# CircuitBoard.net
KiCad netlist of a schematic drawn in EAGLE
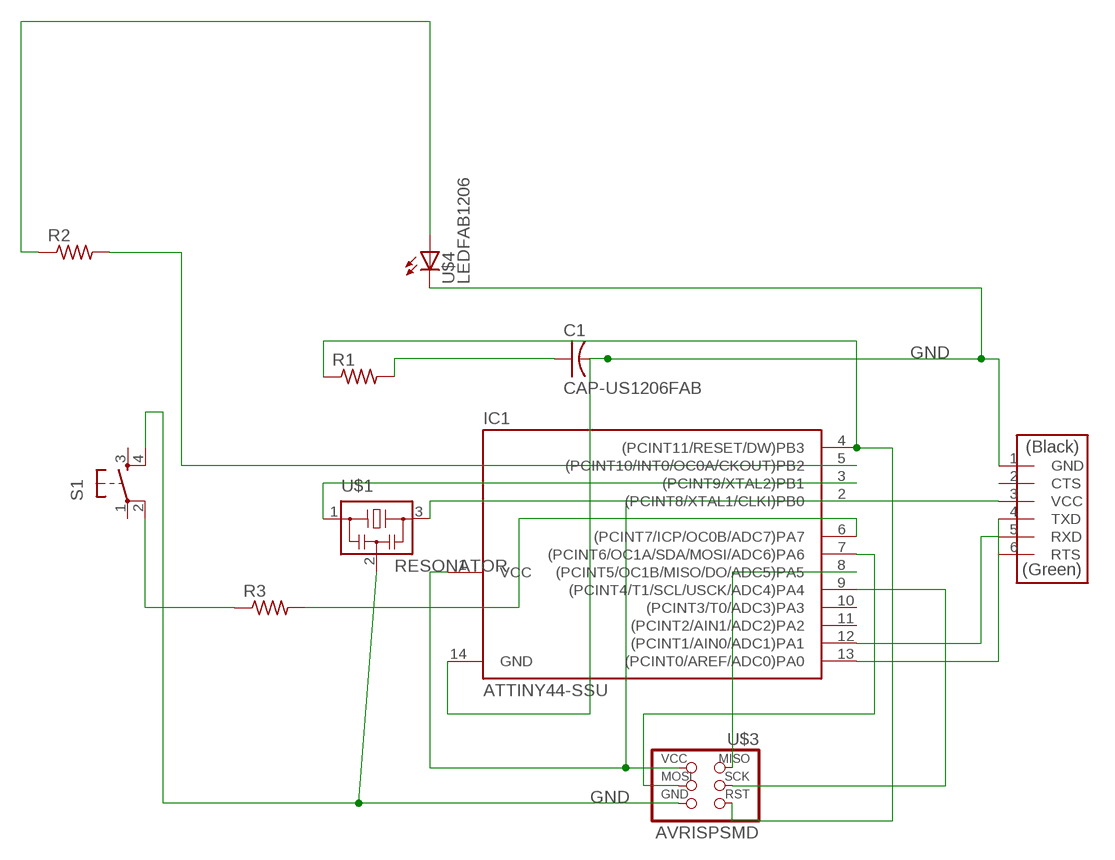
[diagram p0: schematic, sheet 1]

(export (version "E")
  (design (tool "Eeschema 10.0.6"))
  (components
    (comp (ref "C1")
      (value "CAP-US1206FAB")
      (footprint "eagle-import:C1206FAB")
      (libsource (lib "eagle-import") (part "CAP-US1206FAB"))
    )
    (comp (ref "IC1")
      (value "ATTINY44-SSU")
      (footprint "eagle-import:SOIC14")
      (libsource (lib "eagle-import") (part "ATTINY44-SSU"))
    )
    (comp (ref "R1")
      (value "RES-US1206FAB")
      (footprint "eagle-import:R1206FAB")
      (libsource (lib "eagle-import") (part "RES-US1206FAB"))
    )
    (comp (ref "R2")
      (value "RES-US1206FAB")
      (footprint "eagle-import:R1206FAB")
      (libsource (lib "eagle-import") (part "RES-US1206FAB"))
    )
    (comp (ref "R3")
      (value "RES-US1206FAB")
      (footprint "eagle-import:R1206FAB")
      (libsource (lib "eagle-import") (part "RES-US1206FAB"))
    )
    (comp (ref "S1")
      (value "6MM_SWITCH6MM_SWITCH")
      (footprint "eagle-import:6MM_SWITCH")
      (libsource (lib "eagle-import") (part "6MM_SWITCH6MM_SWITCH"))
    )
    (comp (ref "U$1")
      (value "RESONATOR")
      (footprint "eagle-import:EFOBM")
      (libsource (lib "eagle-import") (part "RESONATOR"))
    )
    (comp (ref "U$2")
      (value "FTDI-SMD-HEADER")
      (footprint "eagle-import:1X06SMD")
      (libsource (lib "eagle-import") (part "FTDI-SMD-HEADER"))
    )
    (comp (ref "U$3")
      (value "AVRISPSMD")
      (footprint "eagle-import:2X03SMD")
      (libsource (lib "eagle-import") (part "AVRISPSMD"))
    )
    (comp (ref "U$4")
      (value "LEDFAB1206")
      (footprint "eagle-import:LED1206FAB")
      (libsource (lib "eagle-import") (part "LEDFAB1206"))
    )
  )
  (nets
    (net (code "1") (name "/GND") (class "Default")
      (node (ref "C1") (pin "2") (pinfunction "2_2") (pintype "passive"))
      (node (ref "IC1") (pin "14") (pinfunction "GND_14") (pintype "power_in"))
      (node (ref "S1") (pin "4") (pinfunction "S1_4") (pintype "passive"))
      (node (ref "U$1") (pin "2") (pinfunction "2_2") (pintype "passive"))
      (node (ref "U$2") (pin "1") (pinfunction "GND_1") (pintype "bidirectional"))
      (node (ref "U$3") (pin "6") (pinfunction "GND_6") (pintype "passive"))
      (node (ref "U$4") (pin "2") (pinfunction "C_2") (pintype "passive"))
    )
    (net (code "2") (name "Net-(C1-Pad1)") (class "Default")
      (node (ref "C1") (pin "1") (pinfunction "1_1") (pintype "passive"))
      (node (ref "R1") (pin "2") (pinfunction "2_2") (pintype "passive"))
    )
    (net (code "3") (name "Net-(IC1-(PCINT0{slash}AREF{slash}ADC0)PA0)") (class "Default")
      (node (ref "IC1") (pin "13") (pinfunction "(PCINT0/AREF/ADC0)PA0_13") (pintype "bidirectional"))
      (node (ref "U$2") (pin "4") (pinfunction "TXD_4") (pintype "bidirectional"))
    )
    (net (code "4") (name "Net-(IC1-(PCINT1{slash}AIN0{slash}ADC1)PA1)") (class "Default")
      (node (ref "IC1") (pin "12") (pinfunction "(PCINT1/AIN0/ADC1)PA1_12") (pintype "bidirectional"))
      (node (ref "U$2") (pin "5") (pinfunction "RXD_5") (pintype "bidirectional"))
    )
    (net (code "5") (name "Net-(IC1-(PCINT4{slash}T1{slash}SCL{slash}USCK{slash}ADC4)PA4)") (class "Default")
      (node (ref "IC1") (pin "9") (pinfunction "(PCINT4/T1/SCL/USCK/ADC4)PA4_9") (pintype "bidirectional"))
      (node (ref "U$3") (pin "3") (pinfunction "SCK_3") (pintype "passive"))
    )
    (net (code "6") (name "Net-(IC1-(PCINT5{slash}OC1B{slash}MISO{slash}DO{slash}ADC5)PA5)") (class "Default")
      (node (ref "IC1") (pin "8") (pinfunction "(PCINT5/OC1B/MISO/DO/ADC5)PA5_8") (pintype "bidirectional"))
      (node (ref "U$3") (pin "1") (pinfunction "MISO_1") (pintype "passive"))
    )
    (net (code "7") (name "Net-(IC1-(PCINT6{slash}OC1A{slash}SDA{slash}MOSI{slash}ADC6)PA6)") (class "Default")
      (node (ref "IC1") (pin "7") (pinfunction "(PCINT6/OC1A/SDA/MOSI/ADC6)PA6_7") (pintype "bidirectional"))
      (node (ref "U$3") (pin "4") (pinfunction "MOSI_4") (pintype "passive"))
    )
    (net (code "8") (name "Net-(IC1-(PCINT7{slash}ICP{slash}OC0B{slash}ADC7)PA7)") (class "Default")
      (node (ref "IC1") (pin "6") (pinfunction "(PCINT7/ICP/OC0B/ADC7)PA7_6") (pintype "bidirectional"))
      (node (ref "R3") (pin "2") (pinfunction "2_2") (pintype "passive"))
    )
    (net (code "9") (name "Net-(IC1-(PCINT8{slash}XTAL1{slash}CLKI)PB0)") (class "Default")
      (node (ref "IC1") (pin "2") (pinfunction "(PCINT8/XTAL1/CLKI)PB0_2") (pintype "bidirectional"))
      (node (ref "U$1") (pin "3") (pinfunction "3_3") (pintype "passive"))
    )
    (net (code "10") (name "Net-(IC1-(PCINT9{slash}XTAL2)PB1)") (class "Default")
      (node (ref "IC1") (pin "3") (pinfunction "(PCINT9/XTAL2)PB1_3") (pintype "bidirectional"))
      (node (ref "U$1") (pin "1") (pinfunction "1_1") (pintype "passive"))
    )
    (net (code "11") (name "Net-(IC1-(PCINT10{slash}INT0{slash}OC0A{slash}CKOUT)PB2)") (class "Default")
      (node (ref "IC1") (pin "5") (pinfunction "(PCINT10/INT0/OC0A/CKOUT)PB2_5") (pintype "bidirectional"))
      (node (ref "R2") (pin "2") (pinfunction "2_2") (pintype "passive"))
    )
    (net (code "12") (name "Net-(IC1-(PCINT11{slash}RESET{slash}DW)PB3)") (class "Default")
      (node (ref "IC1") (pin "4") (pinfunction "(PCINT11/RESET/DW)PB3_4") (pintype "bidirectional"))
      (node (ref "R1") (pin "1") (pinfunction "1_1") (pintype "passive"))
      (node (ref "U$3") (pin "5") (pinfunction "RST_5") (pintype "passive"))
    )
    (net (code "13") (name "Net-(IC1-VCC)") (class "Default")
      (node (ref "IC1") (pin "1") (pinfunction "VCC_1") (pintype "power_in"))
      (node (ref "U$2") (pin "3") (pinfunction "VCC_3") (pintype "bidirectional"))
      (node (ref "U$3") (pin "2") (pinfunction "VCC_2") (pintype "passive"))
    )
    (net (code "14") (name "Net-(S1-P1)") (class "Default")
      (node (ref "R3") (pin "1") (pinfunction "1_1") (pintype "passive"))
      (node (ref "S1") (pin "2") (pinfunction "P1_2") (pintype "passive"))
    )
    (net (code "15") (name "Net-(U$4-A)") (class "Default")
      (node (ref "R2") (pin "1") (pinfunction "1_1") (pintype "passive"))
      (node (ref "U$4") (pin "1") (pinfunction "A_1") (pintype "passive"))
    )
    (net (code "16") (name "unconnected-(IC1-(PCINT2{slash}AIN1{slash}ADC2)PA2-Pad11)") (class "Default")
      (node (ref "IC1") (pin "11") (pinfunction "(PCINT2/AIN1/ADC2)PA2_11") (pintype "bidirectional"))
    )
    (net (code "17") (name "unconnected-(IC1-(PCINT3{slash}T0{slash}ADC3)PA3-Pad10)") (class "Default")
      (node (ref "IC1") (pin "10") (pinfunction "(PCINT3/T0/ADC3)PA3_10") (pintype "bidirectional"))
    )
    (net (code "18") (name "unconnected-(S1-P-Pad1)") (class "Default")
      (node (ref "S1") (pin "1") (pinfunction "P_1") (pintype "passive"))
    )
    (net (code "19") (name "unconnected-(S1-S-Pad3)") (class "Default")
      (node (ref "S1") (pin "3") (pinfunction "S_3") (pintype "passive"))
    )
    (net (code "20") (name "unconnected-(U$2-CTS-Pad2)") (class "Default")
      (node (ref "U$2") (pin "2") (pinfunction "CTS_2") (pintype "bidirectional"))
    )
    (net (code "21") (name "unconnected-(U$2-RTS-Pad6)") (class "Default")
      (node (ref "U$2") (pin "6") (pinfunction "RTS_6") (pintype "bidirectional"))
    )
  )
)
